# Main_Camera_Board7.net
KiCad netlist of a schematic drawn in EAGLE
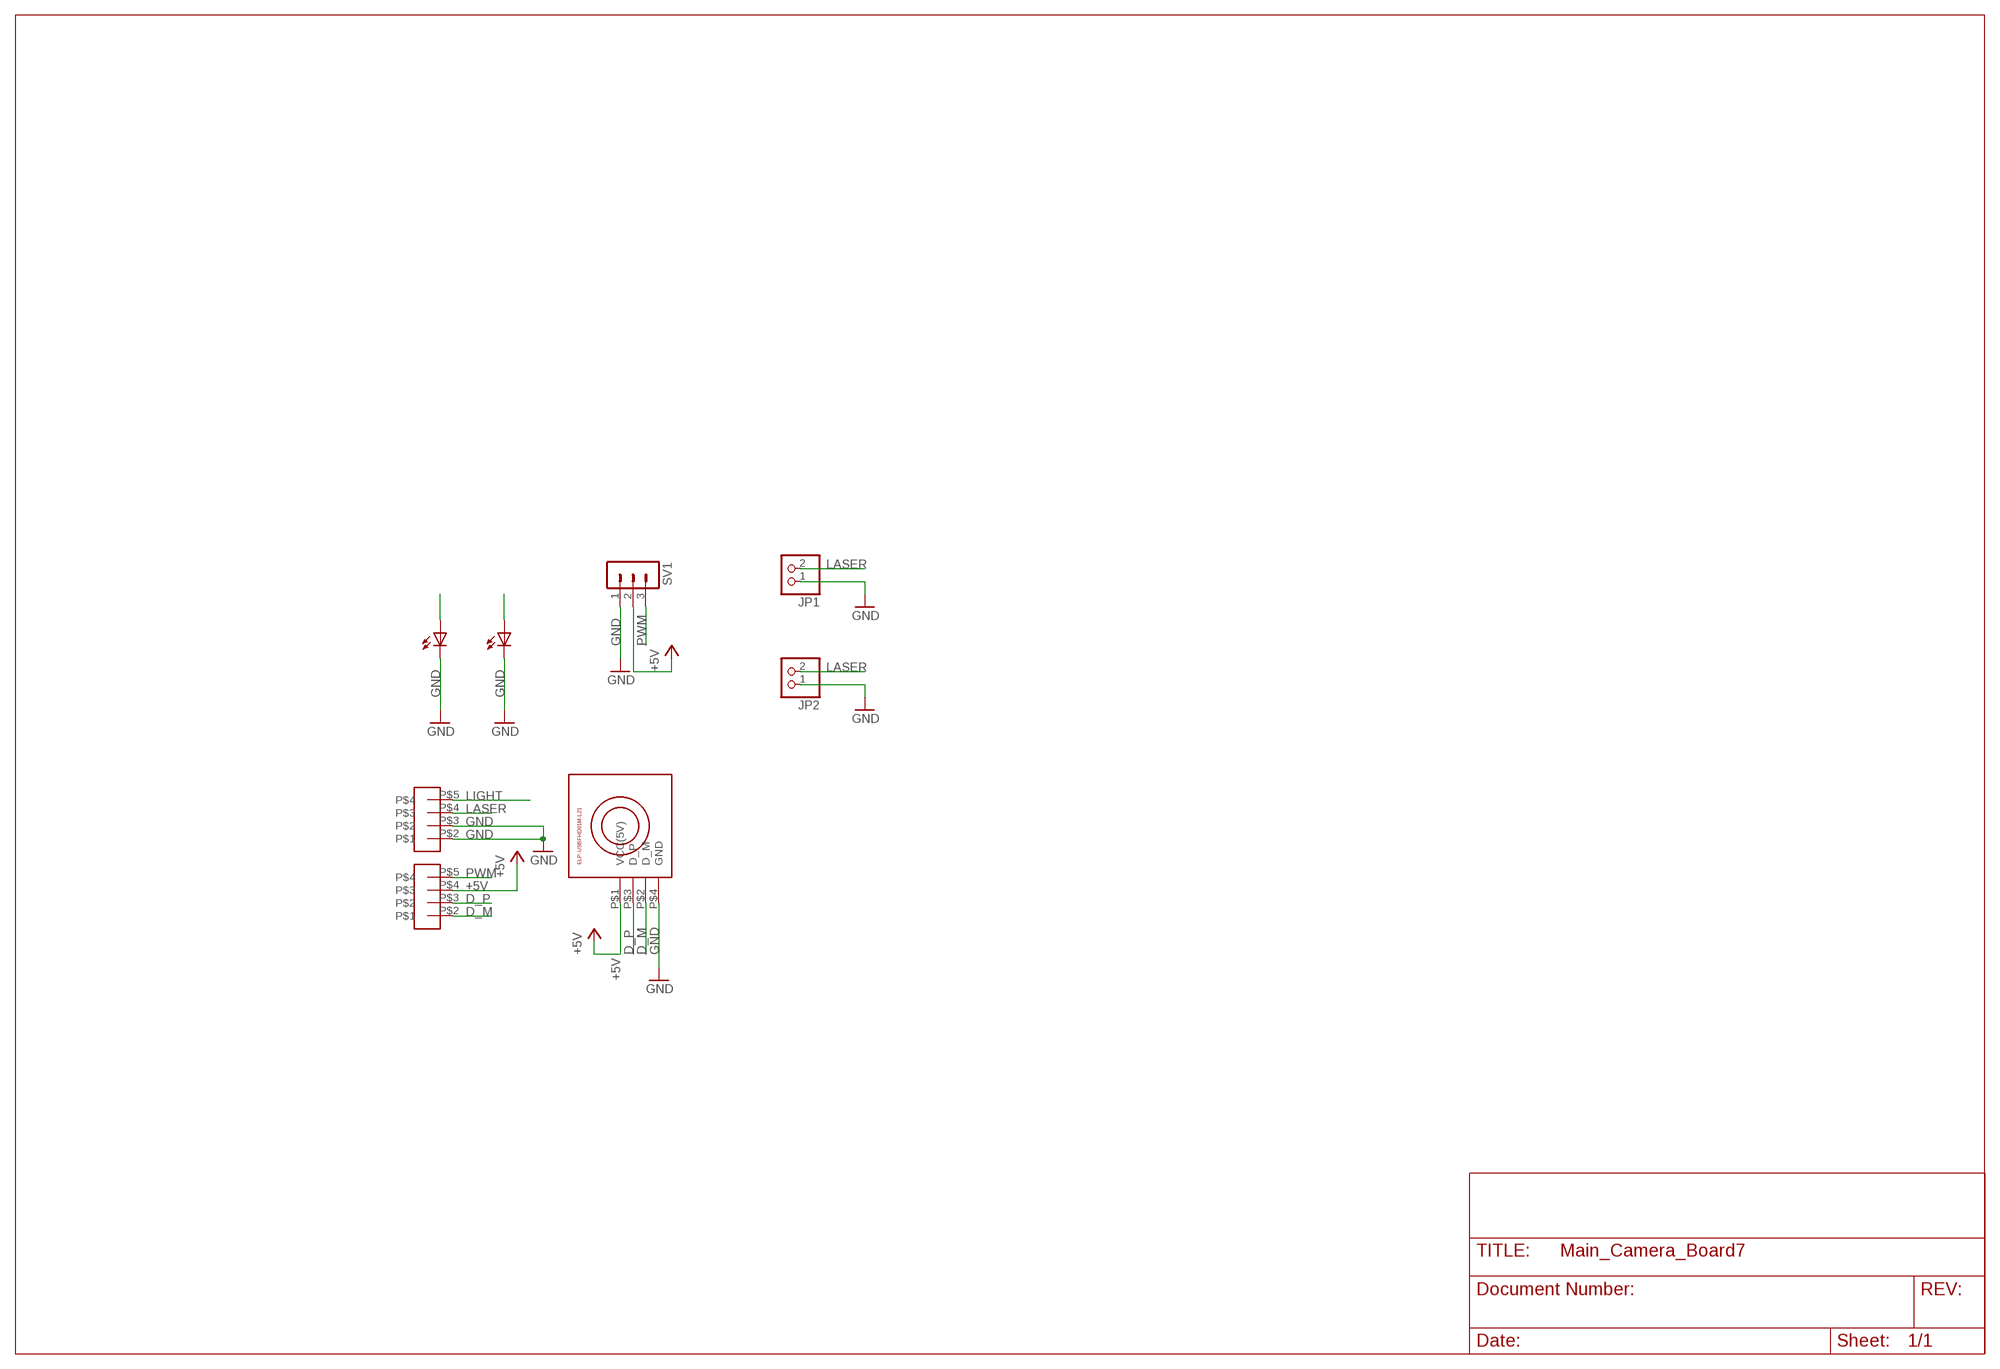
[diagram p0: schematic, sheet 1]

(export (version "E")
  (design (tool "Eeschema 10.0.6"))
  (components
    (comp (ref "JP1")
      (value "PINHD-1X2")
      (footprint "eagle-import:1X02")
      (libsource (lib "eagle-import") (part "PINHD-1X2"))
    )
    (comp (ref "JP2")
      (value "PINHD-1X2")
      (footprint "eagle-import:1X02")
      (libsource (lib "eagle-import") (part "PINHD-1X2"))
    )
    (comp (ref "SV1")
      (value "MA03-1")
      (footprint "eagle-import:MA03-1")
      (libsource (lib "eagle-import") (part "MA03-1"))
    )
    (comp (ref "U$1")
      (value "ELP-USBFHD01M-L21")
      (footprint "eagle-import:ELP-USBFHD01M-L21")
      (libsource (lib "eagle-import") (part "ELP-USBFHD01M-L21"))
    )
    (comp (ref "U$2")
      (value "LED")
      (footprint "eagle-import:LED")
      (libsource (lib "eagle-import") (part "LED"))
    )
    (comp (ref "U$3")
      (value "LED")
      (footprint "eagle-import:LED")
      (libsource (lib "eagle-import") (part "LED"))
    )
    (comp (ref "U$4")
      (value "T21")
      (footprint "eagle-import:T2I")
      (libsource (lib "eagle-import") (part "T21"))
    )
    (comp (ref "U$5")
      (value "T21")
      (footprint "eagle-import:T2I")
      (libsource (lib "eagle-import") (part "T21"))
    )
  )
  (nets
    (net (code "1") (name "+5V") (class "Default")
      (node (ref "SV1") (pin "2") (pinfunction "2_2") (pintype "passive"))
      (node (ref "U$1") (pin "P$1") (pinfunction "VCC(5V)_P$1") (pintype "bidirectional"))
      (node (ref "U$5") (pin "P$4") (pinfunction "P$3_P$4") (pintype "bidirectional"))
    )
    (net (code "2") (name "/D_M") (class "Default")
      (node (ref "U$1") (pin "P$2") (pinfunction "D_M_P$2") (pintype "bidirectional"))
      (node (ref "U$5") (pin "P$2") (pinfunction "P$1_P$2") (pintype "bidirectional"))
    )
    (net (code "3") (name "/D_P") (class "Default")
      (node (ref "U$1") (pin "P$3") (pinfunction "D_P_P$3") (pintype "bidirectional"))
      (node (ref "U$5") (pin "P$3") (pinfunction "P$2_P$3") (pintype "bidirectional"))
    )
    (net (code "4") (name "/LASER") (class "Default")
      (node (ref "JP1") (pin "2") (pinfunction "2_2") (pintype "passive"))
      (node (ref "JP2") (pin "2") (pinfunction "2_2") (pintype "passive"))
      (node (ref "U$4") (pin "P$4") (pinfunction "P$3_P$4") (pintype "bidirectional"))
    )
    (net (code "5") (name "/LIGHT") (class "Default")
      (node (ref "U$2") (pin "P$2") (pinfunction "ANODE_P$2") (pintype "passive"))
      (node (ref "U$3") (pin "P$2") (pinfunction "ANODE_P$2") (pintype "passive"))
      (node (ref "U$4") (pin "P$5") (pinfunction "P$4_P$5") (pintype "bidirectional"))
    )
    (net (code "6") (name "/PWM") (class "Default")
      (node (ref "SV1") (pin "3") (pinfunction "3_3") (pintype "passive"))
      (node (ref "U$5") (pin "P$5") (pinfunction "P$4_P$5") (pintype "bidirectional"))
    )
    (net (code "7") (name "GND") (class "Default")
      (node (ref "JP1") (pin "1") (pinfunction "1_1") (pintype "passive"))
      (node (ref "JP2") (pin "1") (pinfunction "1_1") (pintype "passive"))
      (node (ref "SV1") (pin "1") (pinfunction "1_1") (pintype "passive"))
      (node (ref "U$1") (pin "P$4") (pinfunction "GND_P$4") (pintype "bidirectional"))
      (node (ref "U$2") (pin "P$1") (pinfunction "CATHODE_P$1") (pintype "passive"))
      (node (ref "U$2") (pin "P$3") (pinfunction "CATHODE_P$3") (pintype "passive"))
      (node (ref "U$3") (pin "P$1") (pinfunction "CATHODE_P$1") (pintype "passive"))
      (node (ref "U$3") (pin "P$3") (pinfunction "CATHODE_P$3") (pintype "passive"))
      (node (ref "U$4") (pin "P$2") (pinfunction "P$1_P$2") (pintype "bidirectional"))
      (node (ref "U$4") (pin "P$3") (pinfunction "P$2_P$3") (pintype "bidirectional"))
    )
  )
)
